# ESP8266_MainBoard.net
KiCad netlist of a schematic drawn in EAGLE
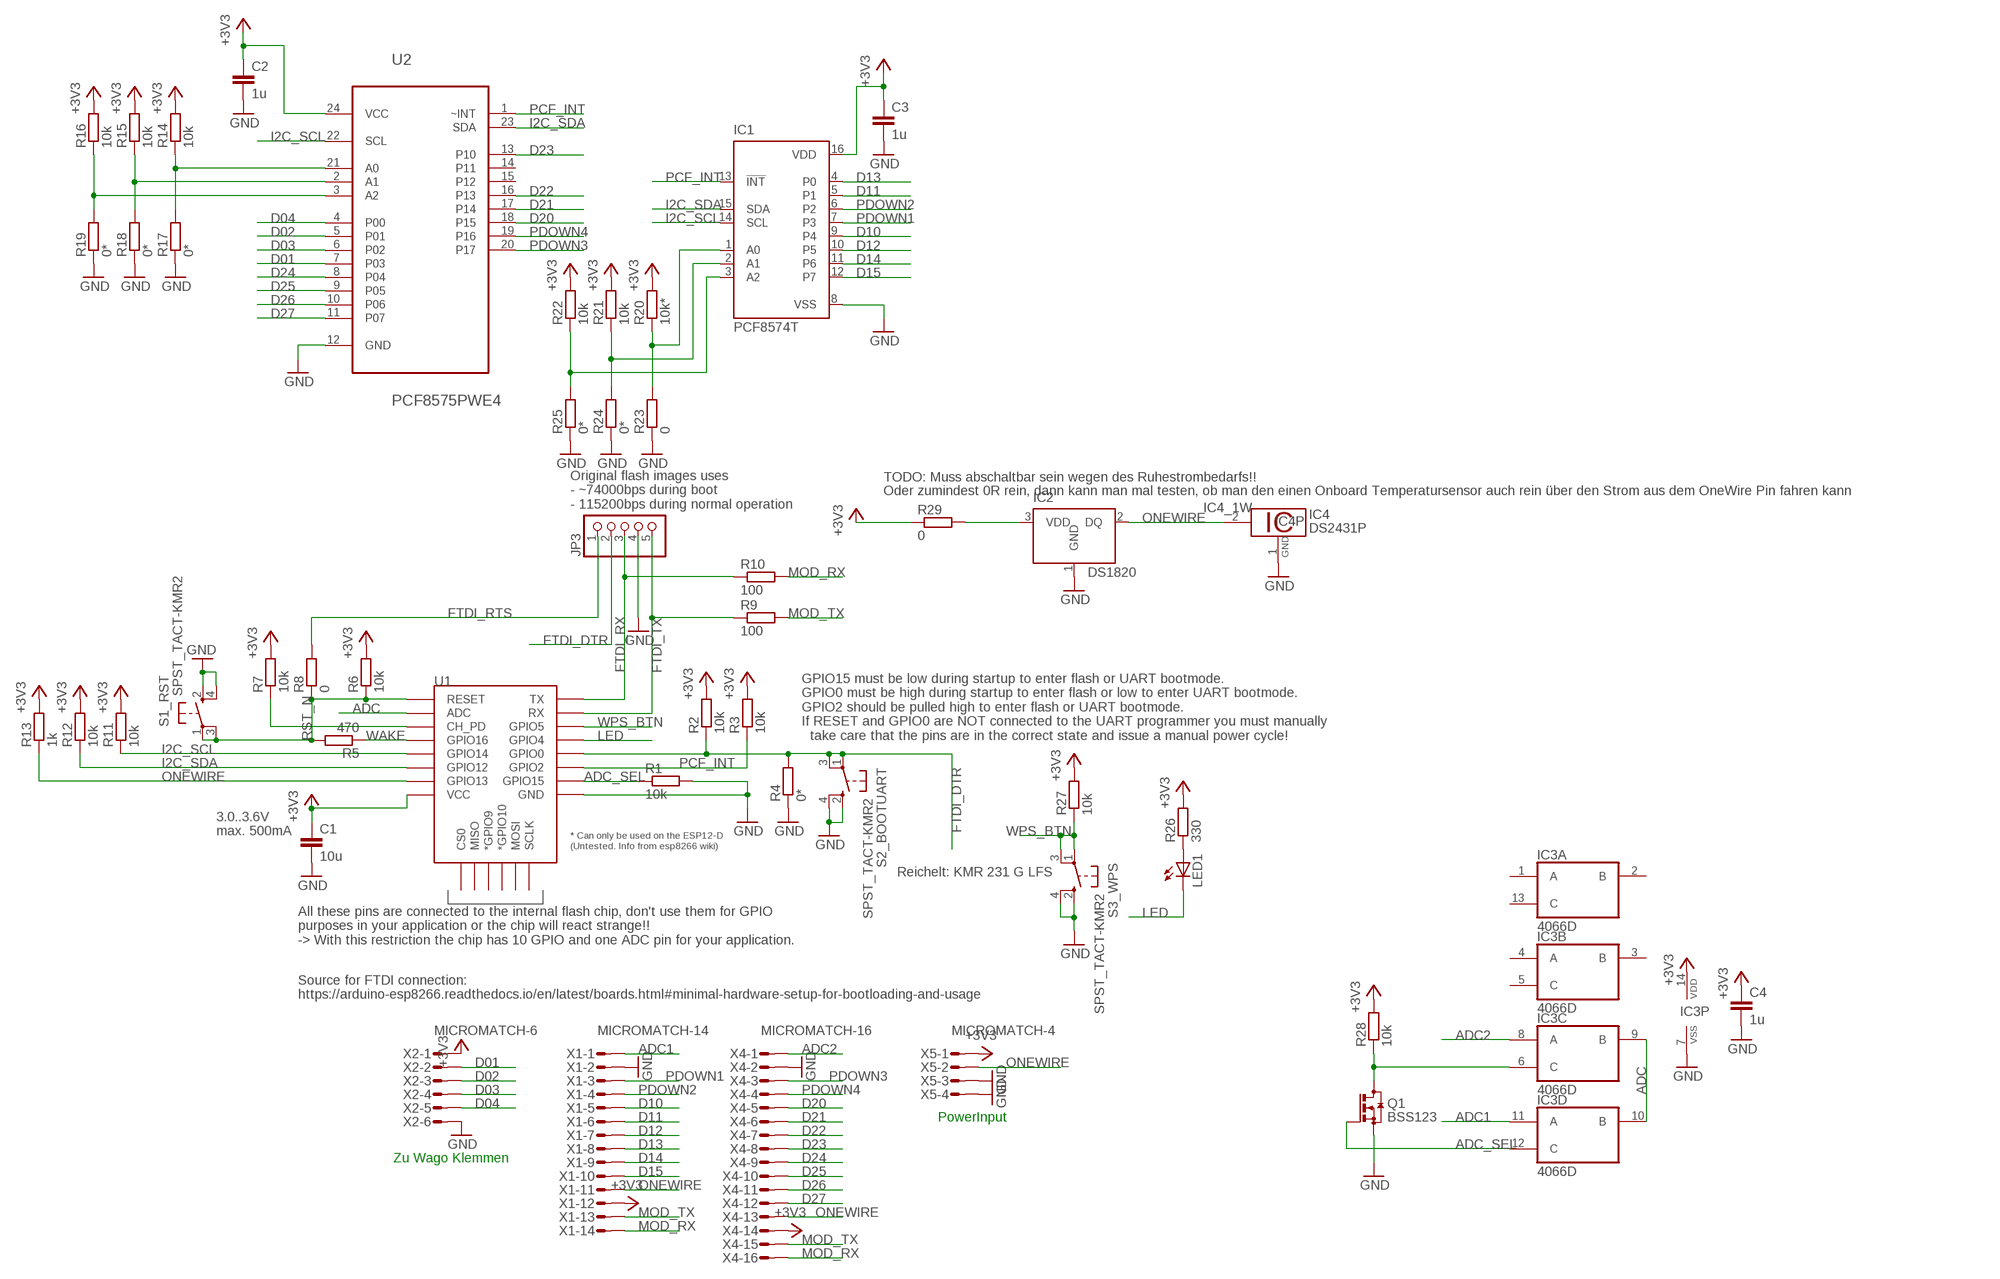
[diagram p0: schematic, sheet 1]

(export (version "E")
  (design (tool "Eeschema 10.0.6"))
  (components
    (comp (ref "C1")
      (value "10u")
      (footprint "eagle-import:C0805")
      (libsource (lib "eagle-import") (part "C-EUC0805"))
    )
    (comp (ref "C2")
      (value "1u")
      (footprint "eagle-import:C0402")
      (libsource (lib "eagle-import") (part "C-EUC0402"))
    )
    (comp (ref "C3")
      (value "1u")
      (footprint "eagle-import:C0402")
      (libsource (lib "eagle-import") (part "C-EUC0402"))
    )
    (comp (ref "C4")
      (value "1u")
      (footprint "eagle-import:C0402")
      (libsource (lib "eagle-import") (part "C-EUC0402"))
    )
    (comp (ref "IC1")
      (value "PCF8574T")
      (footprint "eagle-import:SO16W")
      (fields (field (name "MPN") "PCF8574T/3,512"))
      (libsource (lib "eagle-import") (part "PCF8574T"))
    )
    (comp (ref "IC2")
      (value "DS1820")
      (footprint "eagle-import:TO-92")
      (libsource (lib "eagle-import") (part "DS1820"))
    )
    (comp (ref "IC3")
      (value "4066D")
      (footprint "eagle-import:SO14")
      (libsource (lib "eagle-import") (part "4066D"))
    )
    (comp (ref "IC4")
      (value "DS2431P")
      (footprint "eagle-import:TSOC6")
      (libsource (lib "eagle-import") (part "DS2431P"))
    )
    (comp (ref "JP3")
      (value "PINHD-1X5")
      (footprint "eagle-import:1X05")
      (libsource (lib "eagle-import") (part "PINHD-1X5"))
    )
    (comp (ref "LED1")
      (value "LEDCHIP-LED0603")
      (footprint "eagle-import:CHIP-LED0603")
      (libsource (lib "eagle-import") (part "LEDCHIP-LED0603"))
    )
    (comp (ref "Q1")
      (value "BSS123")
      (footprint "eagle-import:SOT23")
      (libsource (lib "eagle-import") (part "BSS123"))
    )
    (comp (ref "R1")
      (value "10k")
      (footprint "eagle-import:R0402")
      (libsource (lib "eagle-import") (part "R-EU_R0402"))
    )
    (comp (ref "R2")
      (value "10k")
      (footprint "eagle-import:R0402")
      (libsource (lib "eagle-import") (part "R-EU_R0402"))
    )
    (comp (ref "R3")
      (value "10k")
      (footprint "eagle-import:R0402")
      (libsource (lib "eagle-import") (part "R-EU_R0402"))
    )
    (comp (ref "R4")
      (value "0*")
      (footprint "eagle-import:R0402")
      (libsource (lib "eagle-import") (part "R-EU_R0402"))
    )
    (comp (ref "R5")
      (value "470")
      (footprint "eagle-import:R0402")
      (libsource (lib "eagle-import") (part "R-EU_R0402"))
    )
    (comp (ref "R6")
      (value "10k")
      (footprint "eagle-import:R0402")
      (libsource (lib "eagle-import") (part "R-EU_R0402"))
    )
    (comp (ref "R7")
      (value "10k")
      (footprint "eagle-import:R0402")
      (libsource (lib "eagle-import") (part "R-EU_R0402"))
    )
    (comp (ref "R8")
      (value "0")
      (footprint "eagle-import:R0402")
      (libsource (lib "eagle-import") (part "R-EU_R0402"))
    )
    (comp (ref "R9")
      (value "100")
      (footprint "eagle-import:R0402")
      (libsource (lib "eagle-import") (part "R-EU_R0402"))
    )
    (comp (ref "R10")
      (value "100")
      (footprint "eagle-import:R0402")
      (libsource (lib "eagle-import") (part "R-EU_R0402"))
    )
    (comp (ref "R11")
      (value "10k")
      (footprint "eagle-import:R0402")
      (libsource (lib "eagle-import") (part "R-EU_R0402"))
    )
    (comp (ref "R12")
      (value "10k")
      (footprint "eagle-import:R0402")
      (libsource (lib "eagle-import") (part "R-EU_R0402"))
    )
    (comp (ref "R13")
      (value "1k")
      (footprint "eagle-import:R0402")
      (libsource (lib "eagle-import") (part "R-EU_R0402"))
    )
    (comp (ref "R14")
      (value "10k")
      (footprint "eagle-import:R0402")
      (libsource (lib "eagle-import") (part "R-EU_R0402"))
    )
    (comp (ref "R15")
      (value "10k")
      (footprint "eagle-import:R0402")
      (libsource (lib "eagle-import") (part "R-EU_R0402"))
    )
    (comp (ref "R16")
      (value "10k")
      (footprint "eagle-import:R0402")
      (libsource (lib "eagle-import") (part "R-EU_R0402"))
    )
    (comp (ref "R17")
      (value "0*")
      (footprint "eagle-import:R0402")
      (libsource (lib "eagle-import") (part "R-EU_R0402"))
    )
    (comp (ref "R18")
      (value "0*")
      (footprint "eagle-import:R0402")
      (libsource (lib "eagle-import") (part "R-EU_R0402"))
    )
    (comp (ref "R19")
      (value "0*")
      (footprint "eagle-import:R0402")
      (libsource (lib "eagle-import") (part "R-EU_R0402"))
    )
    (comp (ref "R20")
      (value "10k*")
      (footprint "eagle-import:R0402")
      (libsource (lib "eagle-import") (part "R-EU_R0402"))
    )
    (comp (ref "R21")
      (value "10k")
      (footprint "eagle-import:R0402")
      (libsource (lib "eagle-import") (part "R-EU_R0402"))
    )
    (comp (ref "R22")
      (value "10k")
      (footprint "eagle-import:R0402")
      (libsource (lib "eagle-import") (part "R-EU_R0402"))
    )
    (comp (ref "R23")
      (value "0")
      (footprint "eagle-import:R0402")
      (libsource (lib "eagle-import") (part "R-EU_R0402"))
    )
    (comp (ref "R24")
      (value "0*")
      (footprint "eagle-import:R0402")
      (libsource (lib "eagle-import") (part "R-EU_R0402"))
    )
    (comp (ref "R25")
      (value "0*")
      (footprint "eagle-import:R0402")
      (libsource (lib "eagle-import") (part "R-EU_R0402"))
    )
    (comp (ref "R26")
      (value "330")
      (footprint "eagle-import:R0402")
      (libsource (lib "eagle-import") (part "R-EU_R0402"))
    )
    (comp (ref "R27")
      (value "10k")
      (footprint "eagle-import:R0402")
      (libsource (lib "eagle-import") (part "R-EU_R0402"))
    )
    (comp (ref "R28")
      (value "10k")
      (footprint "eagle-import:R0402")
      (libsource (lib "eagle-import") (part "R-EU_R0402"))
    )
    (comp (ref "R29")
      (value "0")
      (footprint "eagle-import:R0402")
      (libsource (lib "eagle-import") (part "R-EU_R0402"))
    )
    (comp (ref "S1_RST")
      (value "SPST_TACT-KMR2")
      (footprint "eagle-import:KMR2")
      (libsource (lib "eagle-import") (part "SPST_TACT-KMR2"))
    )
    (comp (ref "S2_BOOTUART")
      (value "SPST_TACT-KMR2")
      (footprint "eagle-import:KMR2")
      (libsource (lib "eagle-import") (part "SPST_TACT-KMR2"))
    )
    (comp (ref "S3_WPS")
      (value "SPST_TACT-KMR2")
      (footprint "eagle-import:KMR2")
      (libsource (lib "eagle-import") (part "SPST_TACT-KMR2"))
    )
    (comp (ref "U1")
      (value "ESP12ESMD")
      (footprint "eagle-import:ESP12E-SMD")
      (libsource (lib "eagle-import") (part "ESP12ESMD"))
    )
    (comp (ref "U2")
      (value "PCF8575PWE4")
      (footprint "eagle-import:SOP65P640X120-24N")
      (fields (field (name "MF") "Texas Instruments"))
      (libsource (lib "eagle-import") (part "PCF8575PWE4"))
    )
    (comp (ref "X1")
      (value "MICROMATCH-14")
      (footprint "eagle-import:MICROMATCH-14")
      (fields (field (name "MF") "FARNELL") (field (name "MPN") "8-215464-4"))
      (libsource (lib "eagle-import") (part "MICROMATCH-14"))
    )
    (comp (ref "X2")
      (value "MICROMATCH-6")
      (footprint "eagle-import:MICROMATCH-6")
      (fields (field (name "MPN") "7-215464-6"))
      (libsource (lib "eagle-import") (part "MICROMATCH-6"))
    )
    (comp (ref "X4")
      (value "MICROMATCH-16")
      (footprint "eagle-import:MICROMATCH-16")
      (fields (field (name "MF") "FARNELL") (field (name "MPN") "8-215464-6"))
      (libsource (lib "eagle-import") (part "MICROMATCH-16"))
    )
    (comp (ref "X5")
      (value "MICROMATCH-4")
      (footprint "eagle-import:MICROMATCH-4")
      (fields (field (name "MPN") "7-215464-4"))
      (libsource (lib "eagle-import") (part "MICROMATCH-4"))
    )
  )
  (nets
    (net (code "1") (name "+3V3") (class "Default")
      (node (ref "C1") (pin "1") (pinfunction "1_1") (pintype "passive"))
      (node (ref "C2") (pin "1") (pinfunction "1_1") (pintype "passive"))
      (node (ref "C3") (pin "1") (pinfunction "1_1") (pintype "passive"))
      (node (ref "C4") (pin "1") (pinfunction "1_1") (pintype "passive"))
      (node (ref "IC1") (pin "16") (pinfunction "VDD_16") (pintype "power_in"))
      (node (ref "IC3") (pin "14") (pinfunction "VDD_14") (pintype "power_in"))
      (node (ref "R11") (pin "2") (pinfunction "2_2") (pintype "passive"))
      (node (ref "R12") (pin "2") (pinfunction "2_2") (pintype "passive"))
      (node (ref "R13") (pin "2") (pinfunction "2_2") (pintype "passive"))
      (node (ref "R14") (pin "2") (pinfunction "2_2") (pintype "passive"))
      (node (ref "R15") (pin "2") (pinfunction "2_2") (pintype "passive"))
      (node (ref "R16") (pin "2") (pinfunction "2_2") (pintype "passive"))
      (node (ref "R2") (pin "2") (pinfunction "2_2") (pintype "passive"))
      (node (ref "R20") (pin "2") (pinfunction "2_2") (pintype "passive"))
      (node (ref "R21") (pin "2") (pinfunction "2_2") (pintype "passive"))
      (node (ref "R22") (pin "2") (pinfunction "2_2") (pintype "passive"))
      (node (ref "R26") (pin "2") (pinfunction "2_2") (pintype "passive"))
      (node (ref "R27") (pin "2") (pinfunction "2_2") (pintype "passive"))
      (node (ref "R28") (pin "2") (pinfunction "2_2") (pintype "passive"))
      (node (ref "R29") (pin "1") (pinfunction "1_1") (pintype "passive"))
      (node (ref "R3") (pin "2") (pinfunction "2_2") (pintype "passive"))
      (node (ref "R6") (pin "2") (pinfunction "2_2") (pintype "passive"))
      (node (ref "R7") (pin "2") (pinfunction "2_2") (pintype "passive"))
      (node (ref "U1") (pin "VCC") (pinfunction "VCC_VCC") (pintype "bidirectional"))
      (node (ref "U2") (pin "24") (pinfunction "VCC_24") (pintype "power_in"))
      (node (ref "X1") (pin "12") (pinfunction "S_12") (pintype "passive"))
      (node (ref "X2") (pin "1") (pinfunction "S_1") (pintype "passive"))
      (node (ref "X4") (pin "14") (pinfunction "S_14") (pintype "passive"))
      (node (ref "X5") (pin "1") (pinfunction "S_1") (pintype "passive"))
    )
    (net (code "2") (name "/ADC") (class "Default")
      (node (ref "IC3") (pin "10") (pinfunction "B_10") (pintype "tri_state"))
      (node (ref "IC3") (pin "9") (pinfunction "B_9") (pintype "tri_state"))
      (node (ref "U1") (pin "ADC") (pinfunction "ADC_ADC") (pintype "bidirectional"))
    )
    (net (code "3") (name "/ADC1") (class "Default")
      (node (ref "IC3") (pin "11") (pinfunction "A_11") (pintype "tri_state"))
      (node (ref "X1") (pin "1") (pinfunction "S_1") (pintype "passive"))
    )
    (net (code "4") (name "/ADC2") (class "Default")
      (node (ref "IC3") (pin "8") (pinfunction "A_8") (pintype "tri_state"))
      (node (ref "X4") (pin "1") (pinfunction "S_1") (pintype "passive"))
    )
    (net (code "5") (name "/ADC_SEL") (class "Default")
      (node (ref "IC3") (pin "12") (pinfunction "C_12") (pintype "input"))
      (node (ref "Q1") (pin "1") (pinfunction "G_1") (pintype "passive"))
      (node (ref "R1") (pin "1") (pinfunction "1_1") (pintype "passive"))
      (node (ref "U1") (pin "GPIO15") (pinfunction "GPIO15_GPIO15") (pintype "bidirectional"))
    )
    (net (code "6") (name "/D01") (class "Default")
      (node (ref "U2") (pin "7") (pinfunction "P03_7") (pintype "bidirectional"))
      (node (ref "X2") (pin "2") (pinfunction "S_2") (pintype "passive"))
    )
    (net (code "7") (name "/D02") (class "Default")
      (node (ref "U2") (pin "5") (pinfunction "P01_5") (pintype "bidirectional"))
      (node (ref "X2") (pin "3") (pinfunction "S_3") (pintype "passive"))
    )
    (net (code "8") (name "/D03") (class "Default")
      (node (ref "U2") (pin "6") (pinfunction "P02_6") (pintype "bidirectional"))
      (node (ref "X2") (pin "4") (pinfunction "S_4") (pintype "passive"))
    )
    (net (code "9") (name "/D04") (class "Default")
      (node (ref "U2") (pin "4") (pinfunction "P00_4") (pintype "bidirectional"))
      (node (ref "X2") (pin "5") (pinfunction "S_5") (pintype "passive"))
    )
    (net (code "10") (name "/D10") (class "Default")
      (node (ref "IC1") (pin "9") (pinfunction "P4_9") (pintype "bidirectional"))
      (node (ref "X1") (pin "5") (pinfunction "S_5") (pintype "passive"))
    )
    (net (code "11") (name "/D11") (class "Default")
      (node (ref "IC1") (pin "5") (pinfunction "P1_5") (pintype "bidirectional"))
      (node (ref "X1") (pin "6") (pinfunction "S_6") (pintype "passive"))
    )
    (net (code "12") (name "/D12") (class "Default")
      (node (ref "IC1") (pin "10") (pinfunction "P5_10") (pintype "bidirectional"))
      (node (ref "X1") (pin "7") (pinfunction "S_7") (pintype "passive"))
    )
    (net (code "13") (name "/D13") (class "Default")
      (node (ref "IC1") (pin "4") (pinfunction "P0_4") (pintype "bidirectional"))
      (node (ref "X1") (pin "8") (pinfunction "S_8") (pintype "passive"))
    )
    (net (code "14") (name "/D14") (class "Default")
      (node (ref "IC1") (pin "11") (pinfunction "P6_11") (pintype "bidirectional"))
      (node (ref "X1") (pin "9") (pinfunction "S_9") (pintype "passive"))
    )
    (net (code "15") (name "/D15") (class "Default")
      (node (ref "IC1") (pin "12") (pinfunction "P7_12") (pintype "bidirectional"))
      (node (ref "X1") (pin "10") (pinfunction "S_10") (pintype "passive"))
    )
    (net (code "16") (name "/D20") (class "Default")
      (node (ref "U2") (pin "18") (pinfunction "P15_18") (pintype "bidirectional"))
      (node (ref "X4") (pin "5") (pinfunction "S_5") (pintype "passive"))
    )
    (net (code "17") (name "/D21") (class "Default")
      (node (ref "U2") (pin "17") (pinfunction "P14_17") (pintype "bidirectional"))
      (node (ref "X4") (pin "6") (pinfunction "S_6") (pintype "passive"))
    )
    (net (code "18") (name "/D22") (class "Default")
      (node (ref "U2") (pin "16") (pinfunction "P13_16") (pintype "bidirectional"))
      (node (ref "X4") (pin "7") (pinfunction "S_7") (pintype "passive"))
    )
    (net (code "19") (name "/D23") (class "Default")
      (node (ref "U2") (pin "13") (pinfunction "P10_13") (pintype "bidirectional"))
      (node (ref "X4") (pin "8") (pinfunction "S_8") (pintype "passive"))
    )
    (net (code "20") (name "/D24") (class "Default")
      (node (ref "U2") (pin "8") (pinfunction "P04_8") (pintype "bidirectional"))
      (node (ref "X4") (pin "9") (pinfunction "S_9") (pintype "passive"))
    )
    (net (code "21") (name "/D25") (class "Default")
      (node (ref "U2") (pin "9") (pinfunction "P05_9") (pintype "bidirectional"))
      (node (ref "X4") (pin "10") (pinfunction "S_10") (pintype "passive"))
    )
    (net (code "22") (name "/D26") (class "Default")
      (node (ref "U2") (pin "10") (pinfunction "P06_10") (pintype "bidirectional"))
      (node (ref "X4") (pin "11") (pinfunction "S_11") (pintype "passive"))
    )
    (net (code "23") (name "/D27") (class "Default")
      (node (ref "U2") (pin "11") (pinfunction "P07_11") (pintype "bidirectional"))
      (node (ref "X4") (pin "12") (pinfunction "S_12") (pintype "passive"))
    )
    (net (code "24") (name "/FTDI_DTR") (class "Default")
      (node (ref "JP3") (pin "2") (pinfunction "2_2") (pintype "passive"))
      (node (ref "R2") (pin "1") (pinfunction "1_1") (pintype "passive"))
      (node (ref "R4") (pin "2") (pinfunction "2_2") (pintype "passive"))
      (node (ref "S2_BOOTUART") (pin "1") (pinfunction "P_1") (pintype "passive"))
      (node (ref "S2_BOOTUART") (pin "3") (pinfunction "P1_3") (pintype "passive"))
      (node (ref "U1") (pin "GPIO0") (pinfunction "GPIO0_GPIO0") (pintype "bidirectional"))
    )
    (net (code "25") (name "/FTDI_RTS") (class "Default")
      (node (ref "JP3") (pin "1") (pinfunction "1_1") (pintype "passive"))
      (node (ref "R8") (pin "2") (pinfunction "2_2") (pintype "passive"))
    )
    (net (code "26") (name "/FTDI_RX") (class "Default")
      (node (ref "JP3") (pin "3") (pinfunction "3_3") (pintype "passive"))
      (node (ref "R10") (pin "1") (pinfunction "1_1") (pintype "passive"))
      (node (ref "U1") (pin "TXD0") (pinfunction "TX_TXD0") (pintype "bidirectional"))
    )
    (net (code "27") (name "/FTDI_TX") (class "Default")
      (node (ref "JP3") (pin "5") (pinfunction "5_5") (pintype "passive"))
      (node (ref "R9") (pin "1") (pinfunction "1_1") (pintype "passive"))
      (node (ref "U1") (pin "RXD0") (pinfunction "RX_RXD0") (pintype "bidirectional"))
    )
    (net (code "28") (name "/I2C_SCL") (class "Default")
      (node (ref "IC1") (pin "14") (pinfunction "SCL_14") (pintype "input"))
      (node (ref "R11") (pin "1") (pinfunction "1_1") (pintype "passive"))
      (node (ref "U1") (pin "GPIO14") (pinfunction "GPIO14_GPIO14") (pintype "bidirectional"))
      (node (ref "U2") (pin "22") (pinfunction "SCL_22") (pintype "input"))
    )
    (net (code "29") (name "/I2C_SDA") (class "Default")
      (node (ref "IC1") (pin "15") (pinfunction "SDA_15") (pintype "bidirectional"))
      (node (ref "R12") (pin "1") (pinfunction "1_1") (pintype "passive"))
      (node (ref "U1") (pin "GPIO12") (pinfunction "GPIO12_GPIO12") (pintype "bidirectional"))
      (node (ref "U2") (pin "23") (pinfunction "SDA_23") (pintype "bidirectional"))
    )
    (net (code "30") (name "/LED") (class "Default")
      (node (ref "LED1") (pin "C") (pinfunction "C_C") (pintype "passive"))
      (node (ref "U1") (pin "GPIO4") (pinfunction "GPIO4_GPIO4") (pintype "bidirectional"))
    )
    (net (code "31") (name "/MOD_RX") (class "Default")
      (node (ref "R10") (pin "2") (pinfunction "2_2") (pintype "passive"))
      (node (ref "X1") (pin "14") (pinfunction "S_14") (pintype "passive"))
      (node (ref "X4") (pin "16") (pinfunction "S_16") (pintype "passive"))
    )
    (net (code "32") (name "/MOD_TX") (class "Default")
      (node (ref "R9") (pin "2") (pinfunction "2_2") (pintype "passive"))
      (node (ref "X1") (pin "13") (pinfunction "S_13") (pintype "passive"))
      (node (ref "X4") (pin "15") (pinfunction "S_15") (pintype "passive"))
    )
    (net (code "33") (name "/ONEWIRE") (class "Default")
      (node (ref "IC2") (pin "2") (pinfunction "DQ_2") (pintype "output"))
      (node (ref "IC4") (pin "2") (pinfunction "1W_2") (pintype "power_in"))
      (node (ref "R13") (pin "1") (pinfunction "1_1") (pintype "passive"))
      (node (ref "U1") (pin "GPIO13") (pinfunction "GPIO13_GPIO13") (pintype "bidirectional"))
      (node (ref "X1") (pin "11") (pinfunction "S_11") (pintype "passive"))
      (node (ref "X4") (pin "13") (pinfunction "S_13") (pintype "passive"))
      (node (ref "X5") (pin "2") (pinfunction "S_2") (pintype "passive"))
    )
    (net (code "34") (name "/PCF_INT") (class "Default")
      (node (ref "IC1") (pin "13") (pinfunction "~{INT}_13") (pintype "output"))
      (node (ref "R3") (pin "1") (pinfunction "1_1") (pintype "passive"))
      (node (ref "U1") (pin "GPIO2") (pinfunction "GPIO2_GPIO2") (pintype "bidirectional"))
      (node (ref "U2") (pin "1") (pinfunction "~{INT}_1") (pintype "output"))
    )
    (net (code "35") (name "/PDOWN1") (class "Default")
      (node (ref "IC1") (pin "7") (pinfunction "P3_7") (pintype "bidirectional"))
      (node (ref "X1") (pin "3") (pinfunction "S_3") (pintype "passive"))
    )
    (net (code "36") (name "/PDOWN2") (class "Default")
      (node (ref "IC1") (pin "6") (pinfunction "P2_6") (pintype "bidirectional"))
      (node (ref "X1") (pin "4") (pinfunction "S_4") (pintype "passive"))
    )
    (net (code "37") (name "/PDOWN3") (class "Default")
      (node (ref "U2") (pin "20") (pinfunction "P17_20") (pintype "bidirectional"))
      (node (ref "X4") (pin "3") (pinfunction "S_3") (pintype "passive"))
    )
    (net (code "38") (name "/PDOWN4") (class "Default")
      (node (ref "U2") (pin "19") (pinfunction "P16_19") (pintype "bidirectional"))
      (node (ref "X4") (pin "4") (pinfunction "S_4") (pintype "passive"))
    )
    (net (code "39") (name "/RST_N") (class "Default")
      (node (ref "R5") (pin "2") (pinfunction "2_2") (pintype "passive"))
      (node (ref "R6") (pin "1") (pinfunction "1_1") (pintype "passive"))
      (node (ref "R8") (pin "1") (pinfunction "1_1") (pintype "passive"))
      (node (ref "S1_RST") (pin "1") (pinfunction "P_1") (pintype "passive"))
      (node (ref "S1_RST") (pin "3") (pinfunction "P1_3") (pintype "passive"))
      (node (ref "U1") (pin "RESET") (pinfunction "RESET_RESET") (pintype "bidirectional"))
    )
    (net (code "40") (name "/WAKE") (class "Default")
      (node (ref "R5") (pin "1") (pinfunction "1_1") (pintype "passive"))
      (node (ref "U1") (pin "GPIO16") (pinfunction "GPIO16_GPIO16") (pintype "bidirectional"))
    )
    (net (code "41") (name "/WPS_BTN") (class "Default")
      (node (ref "R27") (pin "1") (pinfunction "1_1") (pintype "passive"))
      (node (ref "S3_WPS") (pin "1") (pinfunction "P_1") (pintype "passive"))
      (node (ref "S3_WPS") (pin "3") (pinfunction "P1_3") (pintype "passive"))
      (node (ref "U1") (pin "GPIO5") (pinfunction "GPIO5_GPIO5") (pintype "bidirectional"))
    )
    (net (code "42") (name "GND") (class "Default")
      (node (ref "C1") (pin "2") (pinfunction "2_2") (pintype "passive"))
      (node (ref "C2") (pin "2") (pinfunction "2_2") (pintype "passive"))
      (node (ref "C3") (pin "2") (pinfunction "2_2") (pintype "passive"))
      (node (ref "C4") (pin "2") (pinfunction "2_2") (pintype "passive"))
      (node (ref "IC1") (pin "8") (pinfunction "VSS_8") (pintype "power_in"))
      (node (ref "IC2") (pin "1") (pinfunction "GND_1") (pintype "power_in"))
      (node (ref "IC3") (pin "7") (pinfunction "VSS_7") (pintype "power_in"))
      (node (ref "IC4") (pin "1") (pinfunction "GND_1") (pintype "power_in"))
      (node (ref "JP3") (pin "4") (pinfunction "4_4") (pintype "passive"))
      (node (ref "Q1") (pin "2") (pinfunction "S_2") (pintype "passive"))
      (node (ref "R1") (pin "2") (pinfunction "2_2") (pintype "passive"))
      (node (ref "R17") (pin "1") (pinfunction "1_1") (pintype "passive"))
      (node (ref "R18") (pin "1") (pinfunction "1_1") (pintype "passive"))
      (node (ref "R19") (pin "1") (pinfunction "1_1") (pintype "passive"))
      (node (ref "R23") (pin "1") (pinfunction "1_1") (pintype "passive"))
      (node (ref "R24") (pin "1") (pinfunction "1_1") (pintype "passive"))
      (node (ref "R25") (pin "1") (pinfunction "1_1") (pintype "passive"))
      (node (ref "R4") (pin "1") (pinfunction "1_1") (pintype "passive"))
      (node (ref "S1_RST") (pin "2") (pinfunction "S_2") (pintype "passive"))
      (node (ref "S1_RST") (pin "4") (pinfunction "S1_4") (pintype "passive"))
      (node (ref "S2_BOOTUART") (pin "2") (pinfunction "S_2") (pintype "passive"))
      (node (ref "S2_BOOTUART") (pin "4") (pinfunction "S1_4") (pintype "passive"))
      (node (ref "S3_WPS") (pin "2") (pinfunction "S_2") (pintype "passive"))
      (node (ref "S3_WPS") (pin "4") (pinfunction "S1_4") (pintype "passive"))
      (node (ref "U1") (pin "GND") (pinfunction "GND_GND") (pintype "bidirectional"))
      (node (ref "U2") (pin "12") (pinfunction "GND_12") (pintype "passive"))
      (node (ref "X1") (pin "2") (pinfunction "S_2") (pintype "passive"))
      (node (ref "X2") (pin "6") (pinfunction "S_6") (pintype "passive"))
      (node (ref "X4") (pin "2") (pinfunction "S_2") (pintype "passive"))
      (node (ref "X5") (pin "3") (pinfunction "S_3") (pintype "passive"))
      (node (ref "X5") (pin "4") (pinfunction "S_4") (pintype "passive"))
    )
    (net (code "43") (name "Net-(IC1-A0)") (class "Default")
      (node (ref "IC1") (pin "1") (pinfunction "A0_1") (pintype "input"))
      (node (ref "R20") (pin "1") (pinfunction "1_1") (pintype "passive"))
      (node (ref "R23") (pin "2") (pinfunction "2_2") (pintype "passive"))
    )
    (net (code "44") (name "Net-(IC1-A1)") (class "Default")
      (node (ref "IC1") (pin "2") (pinfunction "A1_2") (pintype "input"))
      (node (ref "R21") (pin "1") (pinfunction "1_1") (pintype "passive"))
      (node (ref "R24") (pin "2") (pinfunction "2_2") (pintype "passive"))
    )
    (net (code "45") (name "Net-(IC1-A2)") (class "Default")
      (node (ref "IC1") (pin "3") (pinfunction "A2_3") (pintype "input"))
      (node (ref "R22") (pin "1") (pinfunction "1_1") (pintype "passive"))
      (node (ref "R25") (pin "2") (pinfunction "2_2") (pintype "passive"))
    )
    (net (code "46") (name "Net-(IC2-VDD)") (class "Default")
      (node (ref "IC2") (pin "3") (pinfunction "VDD_3") (pintype "input"))
      (node (ref "R29") (pin "2") (pinfunction "2_2") (pintype "passive"))
    )
    (net (code "47") (name "Net-(IC3C-C)") (class "Default")
      (node (ref "IC3") (pin "6") (pinfunction "C_6") (pintype "input"))
      (node (ref "Q1") (pin "3") (pinfunction "D_3") (pintype "passive"))
      (node (ref "R28") (pin "1") (pinfunction "1_1") (pintype "passive"))
    )
    (net (code "48") (name "Net-(LED1-PadA)") (class "Default")
      (node (ref "LED1") (pin "A") (pinfunction "A_A") (pintype "passive"))
      (node (ref "R26") (pin "1") (pinfunction "1_1") (pintype "passive"))
    )
    (net (code "49") (name "Net-(R7-Pad1)") (class "Default")
      (node (ref "R7") (pin "1") (pinfunction "1_1") (pintype "passive"))
      (node (ref "U1") (pin "CH_PD") (pinfunction "CH_PD_CH_PD") (pintype "bidirectional"))
    )
    (net (code "50") (name "Net-(U2-A0)") (class "Default")
      (node (ref "R14") (pin "1") (pinfunction "1_1") (pintype "passive"))
      (node (ref "R17") (pin "2") (pinfunction "2_2") (pintype "passive"))
      (node (ref "U2") (pin "21") (pinfunction "A0_21") (pintype "input"))
    )
    (net (code "51") (name "Net-(U2-A1)") (class "Default")
      (node (ref "R15") (pin "1") (pinfunction "1_1") (pintype "passive"))
      (node (ref "R18") (pin "2") (pinfunction "2_2") (pintype "passive"))
      (node (ref "U2") (pin "2") (pinfunction "A1_2") (pintype "input"))
    )
    (net (code "52") (name "Net-(U2-A2)") (class "Default")
      (node (ref "R16") (pin "1") (pinfunction "1_1") (pintype "passive"))
      (node (ref "R19") (pin "2") (pinfunction "2_2") (pintype "passive"))
      (node (ref "U2") (pin "3") (pinfunction "A2_3") (pintype "input"))
    )
    (net (code "53") (name "unconnected-(IC3A-A-Pad1)") (class "Default")
      (node (ref "IC3") (pin "1") (pinfunction "A_1") (pintype "tri_state"))
    )
    (net (code "54") (name "unconnected-(IC3A-B-Pad2)") (class "Default")
      (node (ref "IC3") (pin "2") (pinfunction "B_2") (pintype "tri_state"))
    )
    (net (code "55") (name "unconnected-(IC3A-C-Pad13)") (class "Default")
      (node (ref "IC3") (pin "13") (pinfunction "C_13") (pintype "input"))
    )
    (net (code "56") (name "unconnected-(IC3B-A-Pad4)") (class "Default")
      (node (ref "IC3") (pin "4") (pinfunction "A_4") (pintype "tri_state"))
    )
    (net (code "57") (name "unconnected-(IC3B-B-Pad3)") (class "Default")
      (node (ref "IC3") (pin "3") (pinfunction "B_3") (pintype "tri_state"))
    )
    (net (code "58") (name "unconnected-(IC3B-C-Pad5)") (class "Default")
      (node (ref "IC3") (pin "5") (pinfunction "C_5") (pintype "input"))
    )
    (net (code "59") (name "unconnected-(U1-*GPIO9-PadGPIO9)") (class "Default")
      (node (ref "U1") (pin "GPIO9") (pinfunction "*GPIO9_GPIO9") (pintype "bidirectional"))
    )
    (net (code "60") (name "unconnected-(U1-*GPIO10-PadGPIO10)") (class "Default")
      (node (ref "U1") (pin "GPIO10") (pinfunction "*GPIO10_GPIO10") (pintype "bidirectional"))
    )
    (net (code "61") (name "unconnected-(U1-PadCS0)") (class "Default")
      (node (ref "U1") (pin "CS0") (pinfunction "CS0_CS0") (pintype "bidirectional"))
    )
    (net (code "62") (name "unconnected-(U1-PadMISO)") (class "Default")
      (node (ref "U1") (pin "MISO") (pinfunction "MISO_MISO") (pintype "bidirectional"))
    )
    (net (code "63") (name "unconnected-(U1-PadMOSI)") (class "Default")
      (node (ref "U1") (pin "MOSI") (pinfunction "MOSI_MOSI") (pintype "bidirectional"))
    )
    (net (code "64") (name "unconnected-(U1-PadSCLK)") (class "Default")
      (node (ref "U1") (pin "SCLK") (pinfunction "SCLK_SCLK") (pintype "bidirectional"))
    )
    (net (code "65") (name "unconnected-(U2-P11-Pad14)") (class "Default")
      (node (ref "U2") (pin "14") (pinfunction "P11_14") (pintype "bidirectional"))
    )
    (net (code "66") (name "unconnected-(U2-P12-Pad15)") (class "Default")
      (node (ref "U2") (pin "15") (pinfunction "P12_15") (pintype "bidirectional"))
    )
  )
)
